# nrf_can.net
KiCad netlist of a schematic drawn in EAGLE
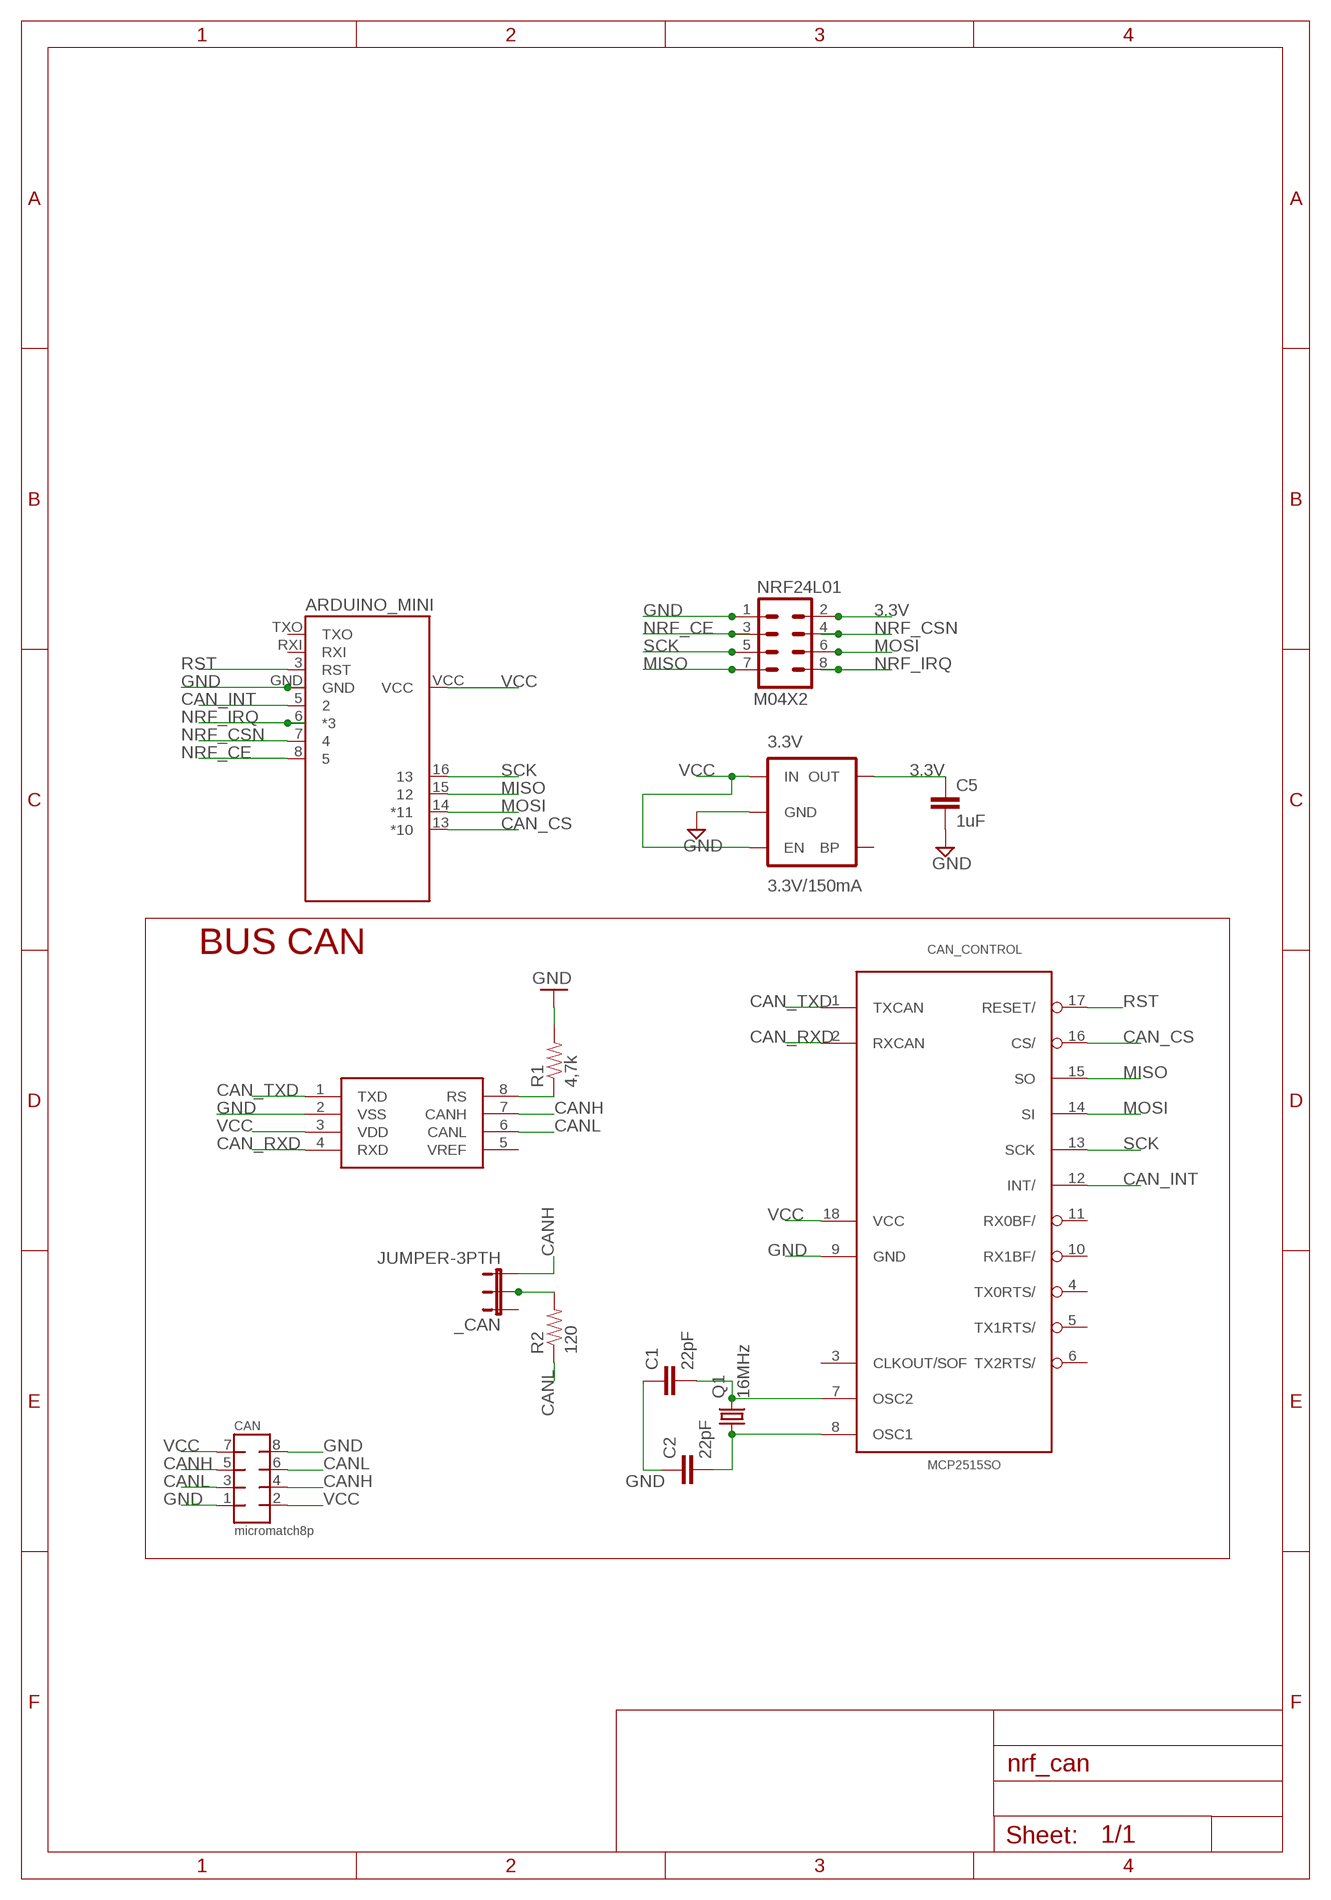
[diagram p0: schematic, sheet 1]

(export (version "E")
  (design (tool "Eeschema 10.0.6"))
  (components
    (comp (ref "3.3V")
      (value "3.3V/150mA")
      (footprint "eagle-import:SOT23-5")
      (libsource (lib "eagle-import") (part "V_REG_MIC52053.3V"))
    )
    (comp (ref "ARDUINO_MINI")
      (value "ARDUINO_PRO_MININRF24L01")
      (footprint "eagle-import:ARDUINO_PRO_MINI")
      (libsource (lib "eagle-import") (part "ARDUINO_PRO_MININRF24L01"))
    )
    (comp (ref "C1")
      (value "22pF")
      (footprint "eagle-import:0805")
      (libsource (lib "eagle-import") (part "CAP0805"))
    )
    (comp (ref "C2")
      (value "22pF")
      (footprint "eagle-import:0805")
      (libsource (lib "eagle-import") (part "CAP0805"))
    )
    (comp (ref "C5")
      (value "1uF")
      (footprint "eagle-import:0805")
      (libsource (lib "eagle-import") (part "CAP0805"))
    )
    (comp (ref "CAN")
      (value "micromatch8p")
      (footprint "eagle-import:AMP-215079-8")
      (libsource (lib "eagle-import") (part "MMATCH-8-PTH"))
    )
    (comp (ref "CAN_CONTROL")
      (value "MCP2515SO")
      (footprint "eagle-import:SO18L")
      (libsource (lib "eagle-import") (part "MCP2515SO"))
    )
    (comp (ref "NRF24L01")
      (value "M04X2")
      (footprint "eagle-import:2X4")
      (libsource (lib "eagle-import") (part "M04X2"))
    )
    (comp (ref "Q1")
      (value "16MHz")
      (footprint "eagle-import:HC49_S")
      (libsource (lib "eagle-import") (part "CRYSTALHC49S"))
    )
    (comp (ref "R1")
      (value "4,7k")
      (footprint "eagle-import:0805")
      (libsource (lib "eagle-import") (part "RESISTOR0805-RES"))
    )
    (comp (ref "R2")
      (value "120")
      (footprint "eagle-import:0805")
      (libsource (lib "eagle-import") (part "RESISTOR0805-RES"))
    )
    (comp (ref "TRANSCEIVER")
      (value "MCP2551")
      (footprint "eagle-import:SO08")
      (libsource (lib "eagle-import") (part "MCP2551"))
    )
    (comp (ref "_CAN")
      (value "JUMPER-3PTH")
      (footprint "eagle-import:1X03")
      (libsource (lib "eagle-import") (part "JUMPER-3PTH"))
    )
  )
  (nets
    (net (code "1") (name "/3.3V") (class "Default")
      (node (ref "3.3V") (pin "5") (pinfunction "OUT_5") (pintype "passive"))
      (node (ref "C5") (pin "1") (pinfunction "1_1") (pintype "passive"))
      (node (ref "NRF24L01") (pin "2") (pinfunction "2_2") (pintype "passive"))
    )
    (net (code "2") (name "/CANH") (class "Default")
      (node (ref "CAN") (pin "4") (pinfunction "4_4") (pintype "bidirectional"))
      (node (ref "CAN") (pin "5") (pinfunction "5_5") (pintype "bidirectional"))
      (node (ref "TRANSCEIVER") (pin "7") (pinfunction "CANH_7") (pintype "bidirectional"))
      (node (ref "_CAN") (pin "3") (pinfunction "3_3") (pintype "passive"))
    )
    (net (code "3") (name "/CANL") (class "Default")
      (node (ref "CAN") (pin "3") (pinfunction "3_3") (pintype "bidirectional"))
      (node (ref "CAN") (pin "6") (pinfunction "6_6") (pintype "bidirectional"))
      (node (ref "R2") (pin "1") (pinfunction "1_1") (pintype "passive"))
      (node (ref "TRANSCEIVER") (pin "6") (pinfunction "CANL_6") (pintype "bidirectional"))
    )
    (net (code "4") (name "/CAN_CS") (class "Default")
      (node (ref "ARDUINO_MINI") (pin "13") (pinfunction "*10_13") (pintype "bidirectional"))
      (node (ref "CAN_CONTROL") (pin "16") (pinfunction "CS/_16") (pintype "input"))
    )
    (net (code "5") (name "/CAN_INT") (class "Default")
      (node (ref "ARDUINO_MINI") (pin "5") (pinfunction "2_5") (pintype "bidirectional"))
      (node (ref "CAN_CONTROL") (pin "12") (pinfunction "INT/_12") (pintype "output"))
    )
    (net (code "6") (name "/CAN_RXD") (class "Default")
      (node (ref "CAN_CONTROL") (pin "2") (pinfunction "RXCAN_2") (pintype "input"))
      (node (ref "TRANSCEIVER") (pin "4") (pinfunction "RXD_4") (pintype "bidirectional"))
    )
    (net (code "7") (name "/CAN_TXD") (class "Default")
      (node (ref "CAN_CONTROL") (pin "1") (pinfunction "TXCAN_1") (pintype "output"))
      (node (ref "TRANSCEIVER") (pin "1") (pinfunction "TXD_1") (pintype "bidirectional"))
    )
    (net (code "8") (name "/MISO") (class "Default")
      (node (ref "ARDUINO_MINI") (pin "15") (pinfunction "12_15") (pintype "bidirectional"))
      (node (ref "CAN_CONTROL") (pin "15") (pinfunction "SO_15") (pintype "output"))
      (node (ref "NRF24L01") (pin "7") (pinfunction "7_7") (pintype "passive"))
    )
    (net (code "9") (name "/MOSI") (class "Default")
      (node (ref "ARDUINO_MINI") (pin "14") (pinfunction "*11_14") (pintype "bidirectional"))
      (node (ref "CAN_CONTROL") (pin "14") (pinfunction "SI_14") (pintype "input"))
      (node (ref "NRF24L01") (pin "6") (pinfunction "6_6") (pintype "passive"))
    )
    (net (code "10") (name "/NRF_CE") (class "Default")
      (node (ref "ARDUINO_MINI") (pin "8") (pinfunction "5_8") (pintype "bidirectional"))
      (node (ref "NRF24L01") (pin "3") (pinfunction "3_3") (pintype "passive"))
    )
    (net (code "11") (name "/NRF_CSN") (class "Default")
      (node (ref "ARDUINO_MINI") (pin "7") (pinfunction "4_7") (pintype "bidirectional"))
      (node (ref "NRF24L01") (pin "4") (pinfunction "4_4") (pintype "passive"))
    )
    (net (code "12") (name "/NRF_IRQ") (class "Default")
      (node (ref "ARDUINO_MINI") (pin "6") (pinfunction "*3_6") (pintype "bidirectional"))
      (node (ref "NRF24L01") (pin "8") (pinfunction "8_8") (pintype "passive"))
    )
    (net (code "13") (name "/RST") (class "Default")
      (node (ref "ARDUINO_MINI") (pin "3") (pinfunction "RST_3") (pintype "bidirectional"))
      (node (ref "CAN_CONTROL") (pin "17") (pinfunction "RESET/_17") (pintype "input"))
    )
    (net (code "14") (name "/SCK") (class "Default")
      (node (ref "ARDUINO_MINI") (pin "16") (pinfunction "13_16") (pintype "bidirectional"))
      (node (ref "CAN_CONTROL") (pin "13") (pinfunction "SCK_13") (pintype "input"))
      (node (ref "NRF24L01") (pin "5") (pinfunction "5_5") (pintype "passive"))
    )
    (net (code "15") (name "/VCC") (class "Default")
      (node (ref "3.3V") (pin "1") (pinfunction "IN_1") (pintype "input"))
      (node (ref "3.3V") (pin "3") (pinfunction "EN_3") (pintype "input"))
      (node (ref "ARDUINO_MINI") (pin "VCC") (pinfunction "VCC_VCC") (pintype "bidirectional"))
      (node (ref "CAN") (pin "2") (pinfunction "2_2") (pintype "bidirectional"))
      (node (ref "CAN") (pin "7") (pinfunction "7_7") (pintype "bidirectional"))
      (node (ref "CAN_CONTROL") (pin "18") (pinfunction "VCC_18") (pintype "power_in"))
      (node (ref "TRANSCEIVER") (pin "3") (pinfunction "VDD_3") (pintype "bidirectional"))
    )
    (net (code "16") (name "GND") (class "Default")
      (node (ref "3.3V") (pin "2") (pinfunction "GND_2") (pintype "input"))
      (node (ref "ARDUINO_MINI") (pin "GND") (pinfunction "GND_GND") (pintype "bidirectional"))
      (node (ref "C1") (pin "1") (pinfunction "1_1") (pintype "passive"))
      (node (ref "C2") (pin "1") (pinfunction "1_1") (pintype "passive"))
      (node (ref "C5") (pin "2") (pinfunction "2_2") (pintype "passive"))
      (node (ref "CAN") (pin "1") (pinfunction "1_1") (pintype "bidirectional"))
      (node (ref "CAN") (pin "8") (pinfunction "8_8") (pintype "bidirectional"))
      (node (ref "CAN_CONTROL") (pin "9") (pinfunction "GND_9") (pintype "power_in"))
      (node (ref "NRF24L01") (pin "1") (pinfunction "1_1") (pintype "passive"))
      (node (ref "R1") (pin "2") (pinfunction "2_2") (pintype "passive"))
      (node (ref "TRANSCEIVER") (pin "2") (pinfunction "VSS_2") (pintype "bidirectional"))
    )
    (net (code "17") (name "Net-(CAN_CONTROL-OSC1)") (class "Default")
      (node (ref "C2") (pin "2") (pinfunction "2_2") (pintype "passive"))
      (node (ref "CAN_CONTROL") (pin "8") (pinfunction "OSC1_8") (pintype "bidirectional"))
      (node (ref "Q1") (pin "1") (pinfunction "1_1") (pintype "passive"))
    )
    (net (code "18") (name "Net-(CAN_CONTROL-OSC2)") (class "Default")
      (node (ref "C1") (pin "2") (pinfunction "2_2") (pintype "passive"))
      (node (ref "CAN_CONTROL") (pin "7") (pinfunction "OSC2_7") (pintype "bidirectional"))
      (node (ref "Q1") (pin "2") (pinfunction "2_2") (pintype "passive"))
    )
    (net (code "19") (name "Net-(R2-Pad2)") (class "Default")
      (node (ref "R2") (pin "2") (pinfunction "2_2") (pintype "passive"))
      (node (ref "_CAN") (pin "2") (pinfunction "2_2") (pintype "passive"))
    )
    (net (code "20") (name "Net-(TRANSCEIVER-RS)") (class "Default")
      (node (ref "R1") (pin "1") (pinfunction "1_1") (pintype "passive"))
      (node (ref "TRANSCEIVER") (pin "8") (pinfunction "RS_8") (pintype "bidirectional"))
    )
    (net (code "21") (name "unconnected-(3.3V-BP-Pad4)") (class "Default")
      (node (ref "3.3V") (pin "4") (pinfunction "BP_4") (pintype "input"))
    )
    (net (code "22") (name "unconnected-(ARDUINO_MINI-PadRXI)") (class "Default")
      (node (ref "ARDUINO_MINI") (pin "RXI") (pinfunction "RXI_RXI") (pintype "bidirectional"))
    )
    (net (code "23") (name "unconnected-(ARDUINO_MINI-PadTXO)") (class "Default")
      (node (ref "ARDUINO_MINI") (pin "TXO") (pinfunction "TXO_TXO") (pintype "bidirectional"))
    )
    (net (code "24") (name "unconnected-(CAN_CONTROL-CLKOUT{slash}SOF-Pad3)") (class "Default")
      (node (ref "CAN_CONTROL") (pin "3") (pinfunction "CLKOUT/SOF_3") (pintype "bidirectional"))
    )
    (net (code "25") (name "unconnected-(CAN_CONTROL-RX0BF{slash}-Pad11)") (class "Default")
      (node (ref "CAN_CONTROL") (pin "11") (pinfunction "RX0BF/_11") (pintype "bidirectional"))
    )
    (net (code "26") (name "unconnected-(CAN_CONTROL-RX1BF{slash}-Pad10)") (class "Default")
      (node (ref "CAN_CONTROL") (pin "10") (pinfunction "RX1BF/_10") (pintype "bidirectional"))
    )
    (net (code "27") (name "unconnected-(CAN_CONTROL-TX0RTS{slash}-Pad4)") (class "Default")
      (node (ref "CAN_CONTROL") (pin "4") (pinfunction "TX0RTS/_4") (pintype "bidirectional"))
    )
    (net (code "28") (name "unconnected-(CAN_CONTROL-TX1RTS{slash}-Pad5)") (class "Default")
      (node (ref "CAN_CONTROL") (pin "5") (pinfunction "TX1RTS/_5") (pintype "bidirectional"))
    )
    (net (code "29") (name "unconnected-(CAN_CONTROL-TX2RTS{slash}-Pad6)") (class "Default")
      (node (ref "CAN_CONTROL") (pin "6") (pinfunction "TX2RTS/_6") (pintype "bidirectional"))
    )
    (net (code "30") (name "unconnected-(TRANSCEIVER-VREF-Pad5)") (class "Default")
      (node (ref "TRANSCEIVER") (pin "5") (pinfunction "VREF_5") (pintype "bidirectional"))
    )
    (net (code "31") (name "unconnected-(_CAN-Pad1)") (class "Default")
      (node (ref "_CAN") (pin "1") (pinfunction "1_1") (pintype "passive"))
    )
  )
)
